# Power_Outlet-RevB.net
KiCad netlist of a schematic drawn in EAGLE
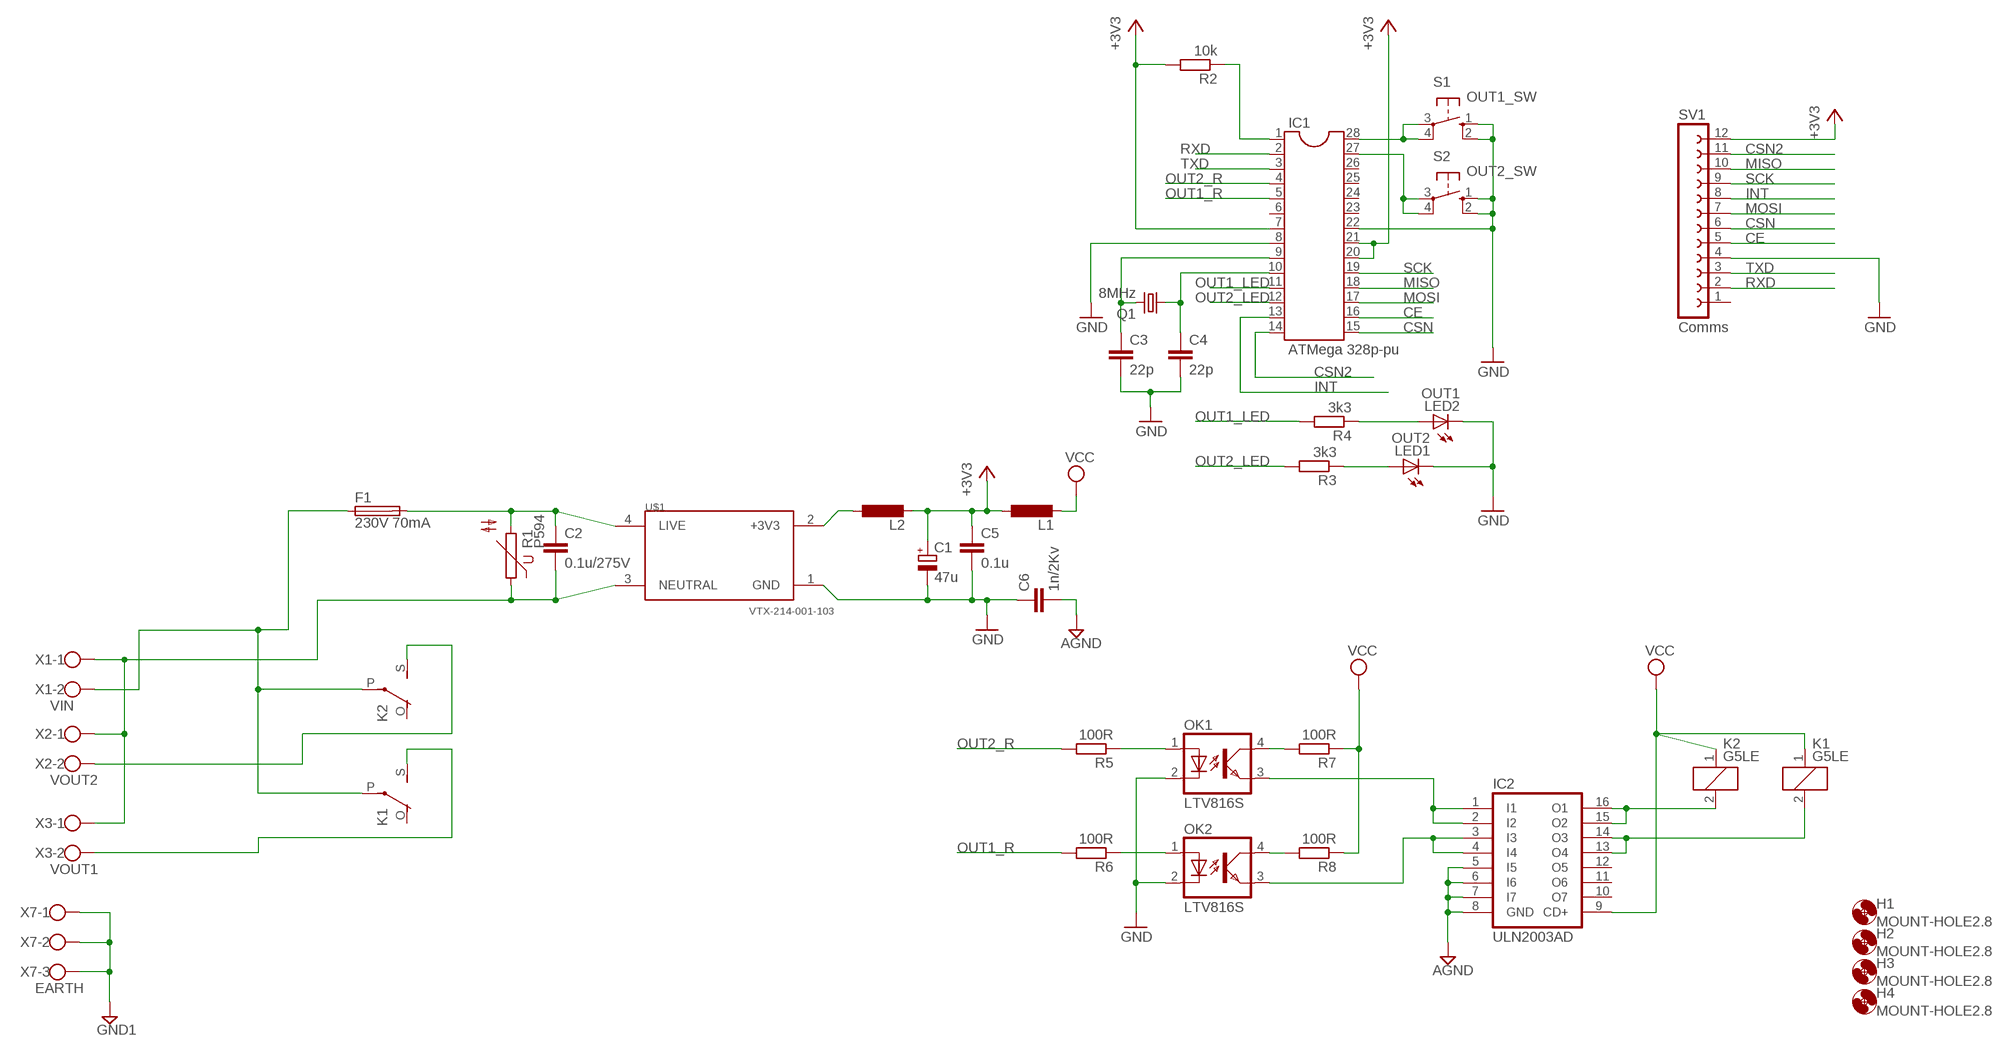
[diagram p0: schematic, sheet 1]

(export (version "E")
  (design (tool "Eeschema 10.0.6"))
  (components
    (comp (ref "C1")
      (value "47u")
      (footprint "eagle-import:E2,5-6E")
      (libsource (lib "eagle-import") (part "CPOL-EUE2,5-6E"))
    )
    (comp (ref "C2")
      (value "0.1u/275V")
      (footprint "eagle-import:C050-030X075")
      (libsource (lib "eagle-import") (part "C-EU050-030X075"))
    )
    (comp (ref "C3")
      (value "22p")
      (footprint "eagle-import:C1206K")
      (libsource (lib "eagle-import") (part "C-EUC1206K"))
    )
    (comp (ref "C4")
      (value "22p")
      (footprint "eagle-import:C1206K")
      (libsource (lib "eagle-import") (part "C-EUC1206K"))
    )
    (comp (ref "C5")
      (value "0.1u")
      (footprint "eagle-import:C1206K")
      (libsource (lib "eagle-import") (part "C-EUC1206K"))
    )
    (comp (ref "C6")
      (value "1n/2Kv")
      (footprint "eagle-import:C1206K")
      (libsource (lib "eagle-import") (part "C-EUC1206K"))
    )
    (comp (ref "F1")
      (value "230V 70mA")
      (footprint "eagle-import:SH22,5A")
      (libsource (lib "eagle-import") (part "FUSESH22,5A"))
    )
    (comp (ref "H1")
      (value "MOUNT-HOLE2.8")
      (footprint "eagle-import:2,8")
      (libsource (lib "eagle-import") (part "MOUNT-HOLE2.8"))
    )
    (comp (ref "H2")
      (value "MOUNT-HOLE2.8")
      (footprint "eagle-import:2,8")
      (libsource (lib "eagle-import") (part "MOUNT-HOLE2.8"))
    )
    (comp (ref "H3")
      (value "MOUNT-HOLE2.8")
      (footprint "eagle-import:2,8")
      (libsource (lib "eagle-import") (part "MOUNT-HOLE2.8"))
    )
    (comp (ref "H4")
      (value "MOUNT-HOLE2.8")
      (footprint "eagle-import:2,8")
      (libsource (lib "eagle-import") (part "MOUNT-HOLE2.8"))
    )
    (comp (ref "IC1")
      (value "ATMega 328p-pu")
      (footprint "eagle-import:DIL28-3")
      (libsource (lib "eagle-import") (part "DIL28-3"))
    )
    (comp (ref "IC2")
      (value "ULN2003AD")
      (footprint "eagle-import:SO16")
      (libsource (lib "eagle-import") (part "ULN2003AD"))
    )
    (comp (ref "K1")
      (value "G5LE")
      (footprint "eagle-import:G5LE")
      (libsource (lib "eagle-import") (part "G5LE"))
    )
    (comp (ref "K2")
      (value "G5LE")
      (footprint "eagle-import:G5LE")
      (libsource (lib "eagle-import") (part "G5LE"))
    )
    (comp (ref "L1")
      (value "L-EUL3225P")
      (footprint "eagle-import:L3225P")
      (libsource (lib "eagle-import") (part "L-EUL3225P"))
    )
    (comp (ref "L2")
      (value "L-EUL3225P")
      (footprint "eagle-import:L3225P")
      (libsource (lib "eagle-import") (part "L-EUL3225P"))
    )
    (comp (ref "LED1")
      (value "OUT2")
      (footprint "eagle-import:LED5MM")
      (libsource (lib "eagle-import") (part "LED5MM"))
    )
    (comp (ref "LED2")
      (value "OUT1")
      (footprint "eagle-import:LED5MM")
      (libsource (lib "eagle-import") (part "LED5MM"))
    )
    (comp (ref "OK1")
      (value "LTV816S")
      (footprint "eagle-import:SMD4")
      (libsource (lib "eagle-import") (part "LTV816S"))
    )
    (comp (ref "OK2")
      (value "LTV816S")
      (footprint "eagle-import:SMD4")
      (libsource (lib "eagle-import") (part "LTV816S"))
    )
    (comp (ref "Q1")
      (value "8MHz")
      (footprint "eagle-import:HC49_S")
      (libsource (lib "eagle-import") (part "CRYSTALHC49S"))
    )
    (comp (ref "R1")
      (value "P594")
      (footprint "eagle-import:P594")
      (libsource (lib "eagle-import") (part "P594"))
    )
    (comp (ref "R2")
      (value "10k")
      (footprint "eagle-import:R1206W")
      (libsource (lib "eagle-import") (part "R-EU_R1206W"))
    )
    (comp (ref "R3")
      (value "3k3")
      (footprint "eagle-import:R1206W")
      (libsource (lib "eagle-import") (part "R-EU_R1206W"))
    )
    (comp (ref "R4")
      (value "3k3")
      (footprint "eagle-import:R1206W")
      (libsource (lib "eagle-import") (part "R-EU_R1206W"))
    )
    (comp (ref "R5")
      (value "100R")
      (footprint "eagle-import:R1206W")
      (libsource (lib "eagle-import") (part "R-EU_R1206W"))
    )
    (comp (ref "R6")
      (value "100R")
      (footprint "eagle-import:R1206W")
      (libsource (lib "eagle-import") (part "R-EU_R1206W"))
    )
    (comp (ref "R7")
      (value "100R")
      (footprint "eagle-import:R1206W")
      (libsource (lib "eagle-import") (part "R-EU_R1206W"))
    )
    (comp (ref "R8")
      (value "100R")
      (footprint "eagle-import:R1206W")
      (libsource (lib "eagle-import") (part "R-EU_R1206W"))
    )
    (comp (ref "S1")
      (value "OUT1_SW")
      (footprint "eagle-import:B3F-40XX")
      (fields (field (name "MF") "OMRON COMPONENTS USA") (field (name "MPN") "B3F-4000"))
      (libsource (lib "eagle-import") (part "40-XX"))
    )
    (comp (ref "S2")
      (value "OUT2_SW")
      (footprint "eagle-import:B3F-40XX")
      (fields (field (name "MF") "OMRON COMPONENTS USA") (field (name "MPN") "B3F-4000"))
      (libsource (lib "eagle-import") (part "40-XX"))
    )
    (comp (ref "SV1")
      (value "Comms")
      (footprint "eagle-import:FE12W")
      (libsource (lib "eagle-import") (part "FE12W"))
    )
    (comp (ref "U$1")
      (value "VTX-214-001-103")
      (footprint "eagle-import:VTX214001103")
      (libsource (lib "eagle-import") (part "VTX-214-001-103"))
    )
    (comp (ref "X1")
      (value "VIN")
      (footprint "eagle-import:W237-102")
      (fields (field (name "MPN") "237-102"))
      (libsource (lib "eagle-import") (part "W237-102"))
    )
    (comp (ref "X2")
      (value "VOUT2")
      (footprint "eagle-import:W237-102")
      (fields (field (name "MPN") "237-102"))
      (libsource (lib "eagle-import") (part "W237-102"))
    )
    (comp (ref "X3")
      (value "VOUT1")
      (footprint "eagle-import:W237-102")
      (fields (field (name "MPN") "237-102"))
      (libsource (lib "eagle-import") (part "W237-102"))
    )
    (comp (ref "X7")
      (value "EARTH")
      (footprint "eagle-import:W237-103")
      (fields (field (name "MPN") "237-103"))
      (libsource (lib "eagle-import") (part "W237-103"))
    )
  )
  (nets
    (net (code "1") (name "+3V3") (class "Default")
      (node (ref "C1") (pin "+") (pinfunction "+_+") (pintype "passive"))
      (node (ref "C5") (pin "1") (pinfunction "1_1") (pintype "passive"))
      (node (ref "IC1") (pin "20") (pinfunction "20_20") (pintype "passive"))
      (node (ref "IC1") (pin "21") (pinfunction "21_21") (pintype "passive"))
      (node (ref "IC1") (pin "7") (pinfunction "7_7") (pintype "passive"))
      (node (ref "L1") (pin "1") (pinfunction "1_1") (pintype "passive"))
      (node (ref "L2") (pin "1") (pinfunction "1_1") (pintype "passive"))
      (node (ref "L2") (pin "2") (pinfunction "2_2") (pintype "passive"))
      (node (ref "R2") (pin "2") (pinfunction "2_2") (pintype "passive"))
      (node (ref "SV1") (pin "12") (pinfunction "12_12") (pintype "passive"))
      (node (ref "U$1") (pin "2") (pinfunction "+3V3_2") (pintype "power_in"))
    )
    (net (code "2") (name "/CE") (class "Default")
      (node (ref "IC1") (pin "16") (pinfunction "16_16") (pintype "passive"))
      (node (ref "SV1") (pin "5") (pinfunction "5_5") (pintype "passive"))
    )
    (net (code "3") (name "/CSN") (class "Default")
      (node (ref "IC1") (pin "15") (pinfunction "15_15") (pintype "passive"))
      (node (ref "SV1") (pin "6") (pinfunction "6_6") (pintype "passive"))
    )
    (net (code "4") (name "/CSN2") (class "Default")
      (node (ref "IC1") (pin "14") (pinfunction "14_14") (pintype "passive"))
      (node (ref "SV1") (pin "11") (pinfunction "11_11") (pintype "passive"))
    )
    (net (code "5") (name "/INT") (class "Default")
      (node (ref "IC1") (pin "13") (pinfunction "13_13") (pintype "passive"))
      (node (ref "SV1") (pin "8") (pinfunction "8_8") (pintype "passive"))
    )
    (net (code "6") (name "/MISO") (class "Default")
      (node (ref "IC1") (pin "18") (pinfunction "18_18") (pintype "passive"))
      (node (ref "SV1") (pin "10") (pinfunction "10_10") (pintype "passive"))
    )
    (net (code "7") (name "/MOSI") (class "Default")
      (node (ref "IC1") (pin "17") (pinfunction "17_17") (pintype "passive"))
      (node (ref "SV1") (pin "7") (pinfunction "7_7") (pintype "passive"))
    )
    (net (code "8") (name "/OUT1_LED") (class "Default")
      (node (ref "IC1") (pin "11") (pinfunction "11_11") (pintype "passive"))
      (node (ref "R4") (pin "2") (pinfunction "2_2") (pintype "passive"))
    )
    (net (code "9") (name "/OUT1_R") (class "Default")
      (node (ref "IC1") (pin "5") (pinfunction "5_5") (pintype "passive"))
      (node (ref "R6") (pin "2") (pinfunction "2_2") (pintype "passive"))
    )
    (net (code "10") (name "/OUT2_LED") (class "Default")
      (node (ref "IC1") (pin "12") (pinfunction "12_12") (pintype "passive"))
      (node (ref "R3") (pin "2") (pinfunction "2_2") (pintype "passive"))
    )
    (net (code "11") (name "/OUT2_R") (class "Default")
      (node (ref "IC1") (pin "4") (pinfunction "4_4") (pintype "passive"))
      (node (ref "R5") (pin "2") (pinfunction "2_2") (pintype "passive"))
    )
    (net (code "12") (name "/RXD") (class "Default")
      (node (ref "IC1") (pin "2") (pinfunction "2_2") (pintype "passive"))
      (node (ref "SV1") (pin "2") (pinfunction "2_2") (pintype "passive"))
    )
    (net (code "13") (name "/SCK") (class "Default")
      (node (ref "IC1") (pin "19") (pinfunction "19_19") (pintype "passive"))
      (node (ref "SV1") (pin "9") (pinfunction "9_9") (pintype "passive"))
    )
    (net (code "14") (name "/TXD") (class "Default")
      (node (ref "IC1") (pin "3") (pinfunction "3_3") (pintype "passive"))
      (node (ref "SV1") (pin "3") (pinfunction "3_3") (pintype "passive"))
    )
    (net (code "15") (name "AGND") (class "Default")
      (node (ref "C6") (pin "2") (pinfunction "2_2") (pintype "passive"))
      (node (ref "IC2") (pin "5") (pinfunction "I5_5") (pintype "input"))
      (node (ref "IC2") (pin "6") (pinfunction "I6_6") (pintype "input"))
      (node (ref "IC2") (pin "7") (pinfunction "I7_7") (pintype "input"))
      (node (ref "IC2") (pin "8") (pinfunction "GND_8") (pintype "power_in"))
    )
    (net (code "16") (name "GND") (class "Default")
      (node (ref "C1") (pin "-") (pinfunction "-_-") (pintype "passive"))
      (node (ref "C3") (pin "2") (pinfunction "2_2") (pintype "passive"))
      (node (ref "C4") (pin "2") (pinfunction "2_2") (pintype "passive"))
      (node (ref "C5") (pin "2") (pinfunction "2_2") (pintype "passive"))
      (node (ref "C6") (pin "1") (pinfunction "1_1") (pintype "passive"))
      (node (ref "IC1") (pin "22") (pinfunction "22_22") (pintype "passive"))
      (node (ref "IC1") (pin "8") (pinfunction "8_8") (pintype "passive"))
      (node (ref "LED1") (pin "K") (pinfunction "C_K") (pintype "passive"))
      (node (ref "LED2") (pin "K") (pinfunction "C_K") (pintype "passive"))
      (node (ref "OK1") (pin "2") (pinfunction "C_2") (pintype "passive"))
      (node (ref "OK2") (pin "2") (pinfunction "C_2") (pintype "passive"))
      (node (ref "S1") (pin "1") (pinfunction "S_1") (pintype "passive"))
      (node (ref "S1") (pin "2") (pinfunction "S1_2") (pintype "passive"))
      (node (ref "S2") (pin "1") (pinfunction "S_1") (pintype "passive"))
      (node (ref "S2") (pin "2") (pinfunction "S1_2") (pintype "passive"))
      (node (ref "SV1") (pin "4") (pinfunction "4_4") (pintype "passive"))
      (node (ref "U$1") (pin "1") (pinfunction "GND_1") (pintype "power_in"))
    )
    (net (code "17") (name "GND1") (class "Default")
      (node (ref "X7") (pin "1") (pinfunction "KL_1") (pintype "passive"))
      (node (ref "X7") (pin "2") (pinfunction "KL_2") (pintype "passive"))
      (node (ref "X7") (pin "3") (pinfunction "KL_3") (pintype "passive"))
    )
    (net (code "18") (name "Net-(C3-Pad1)") (class "Default")
      (node (ref "C3") (pin "1") (pinfunction "1_1") (pintype "passive"))
      (node (ref "IC1") (pin "9") (pinfunction "9_9") (pintype "passive"))
      (node (ref "Q1") (pin "2") (pinfunction "2_2") (pintype "passive"))
    )
    (net (code "19") (name "Net-(C4-Pad1)") (class "Default")
      (node (ref "C4") (pin "1") (pinfunction "1_1") (pintype "passive"))
      (node (ref "IC1") (pin "10") (pinfunction "10_10") (pintype "passive"))
      (node (ref "Q1") (pin "1") (pinfunction "1_1") (pintype "passive"))
    )
    (net (code "20") (name "Net-(IC1-Pad1)") (class "Default")
      (node (ref "IC1") (pin "1") (pinfunction "1_1") (pintype "passive"))
      (node (ref "R2") (pin "1") (pinfunction "1_1") (pintype "passive"))
    )
    (net (code "21") (name "Net-(IC2-I1)") (class "Default")
      (node (ref "IC2") (pin "1") (pinfunction "I1_1") (pintype "input"))
      (node (ref "IC2") (pin "2") (pinfunction "I2_2") (pintype "input"))
      (node (ref "OK1") (pin "3") (pinfunction "EMIT_3") (pintype "passive"))
    )
    (net (code "22") (name "Net-(IC2-I3)") (class "Default")
      (node (ref "IC2") (pin "3") (pinfunction "I3_3") (pintype "input"))
      (node (ref "IC2") (pin "4") (pinfunction "I4_4") (pintype "input"))
      (node (ref "OK2") (pin "3") (pinfunction "EMIT_3") (pintype "passive"))
    )
    (net (code "23") (name "Net-(IC2-O1)") (class "Default")
      (node (ref "IC2") (pin "15") (pinfunction "O2_15") (pintype "open_collector"))
      (node (ref "IC2") (pin "16") (pinfunction "O1_16") (pintype "open_collector"))
      (node (ref "K2") (pin "2") (pinfunction "2_2") (pintype "passive"))
    )
    (net (code "24") (name "Net-(IC2-O3)") (class "Default")
      (node (ref "IC2") (pin "13") (pinfunction "O4_13") (pintype "open_collector"))
      (node (ref "IC2") (pin "14") (pinfunction "O3_14") (pintype "open_collector"))
      (node (ref "K1") (pin "2") (pinfunction "2_2") (pintype "passive"))
    )
    (net (code "25") (name "Net-(LED1-PadA)") (class "Default")
      (node (ref "LED1") (pin "A") (pinfunction "A_A") (pintype "passive"))
      (node (ref "R3") (pin "1") (pinfunction "1_1") (pintype "passive"))
    )
    (net (code "26") (name "Net-(LED2-PadA)") (class "Default")
      (node (ref "LED2") (pin "A") (pinfunction "A_A") (pintype "passive"))
      (node (ref "R4") (pin "1") (pinfunction "1_1") (pintype "passive"))
    )
    (net (code "27") (name "Net-(OK1-A)") (class "Default")
      (node (ref "OK1") (pin "1") (pinfunction "A_1") (pintype "passive"))
      (node (ref "R5") (pin "1") (pinfunction "1_1") (pintype "passive"))
    )
    (net (code "28") (name "Net-(OK1-COL)") (class "Default")
      (node (ref "OK1") (pin "4") (pinfunction "COL_4") (pintype "passive"))
      (node (ref "R7") (pin "2") (pinfunction "2_2") (pintype "passive"))
    )
    (net (code "29") (name "Net-(OK2-A)") (class "Default")
      (node (ref "OK2") (pin "1") (pinfunction "A_1") (pintype "passive"))
      (node (ref "R6") (pin "1") (pinfunction "1_1") (pintype "passive"))
    )
    (net (code "30") (name "Net-(OK2-COL)") (class "Default")
      (node (ref "OK2") (pin "4") (pinfunction "COL_4") (pintype "passive"))
      (node (ref "R8") (pin "2") (pinfunction "2_2") (pintype "passive"))
    )
    (net (code "31") (name "Net-(S1-P)") (class "Default")
      (node (ref "IC1") (pin "28") (pinfunction "28_28") (pintype "passive"))
      (node (ref "S1") (pin "3") (pinfunction "P_3") (pintype "passive"))
      (node (ref "S1") (pin "4") (pinfunction "P1_4") (pintype "passive"))
    )
    (net (code "32") (name "Net-(S2-P)") (class "Default")
      (node (ref "IC1") (pin "27") (pinfunction "27_27") (pintype "passive"))
      (node (ref "S2") (pin "3") (pinfunction "P_3") (pintype "passive"))
      (node (ref "S2") (pin "4") (pinfunction "P1_4") (pintype "passive"))
    )
    (net (code "33") (name "Net-(U$1-LIVE)") (class "Default")
      (node (ref "C2") (pin "1") (pinfunction "1_1") (pintype "passive"))
      (node (ref "F1") (pin "2") (pinfunction "2_2") (pintype "passive"))
      (node (ref "R1") (pin "2") (pinfunction "2_2") (pintype "passive"))
      (node (ref "U$1") (pin "4") (pinfunction "LIVE_4") (pintype "input"))
    )
    (net (code "34") (name "Net-(U$1-NEUTRAL)") (class "Default")
      (node (ref "C2") (pin "2") (pinfunction "2_2") (pintype "passive"))
      (node (ref "R1") (pin "1") (pinfunction "1_1") (pintype "passive"))
      (node (ref "U$1") (pin "3") (pinfunction "NEUTRAL_3") (pintype "input"))
      (node (ref "X1") (pin "1") (pinfunction "KL_1") (pintype "passive"))
      (node (ref "X2") (pin "1") (pinfunction "KL_1") (pintype "passive"))
      (node (ref "X3") (pin "1") (pinfunction "KL_1") (pintype "passive"))
    )
    (net (code "35") (name "Net-(X1B-KL)") (class "Default")
      (node (ref "F1") (pin "1") (pinfunction "1_1") (pintype "passive"))
      (node (ref "K1") (pin "P") (pinfunction "P_P") (pintype "passive"))
      (node (ref "K2") (pin "P") (pinfunction "P_P") (pintype "passive"))
      (node (ref "X1") (pin "2") (pinfunction "KL_2") (pintype "passive"))
    )
    (net (code "36") (name "Net-(X2B-KL)") (class "Default")
      (node (ref "K2") (pin "S") (pinfunction "S_S") (pintype "passive"))
      (node (ref "X2") (pin "2") (pinfunction "KL_2") (pintype "passive"))
    )
    (net (code "37") (name "Net-(X3B-KL)") (class "Default")
      (node (ref "K1") (pin "S") (pinfunction "S_S") (pintype "passive"))
      (node (ref "X3") (pin "2") (pinfunction "KL_2") (pintype "passive"))
    )
    (net (code "38") (name "VCC") (class "Default")
      (node (ref "IC2") (pin "9") (pinfunction "CD+_9") (pintype "passive"))
      (node (ref "K1") (pin "1") (pinfunction "1_1") (pintype "passive"))
      (node (ref "K2") (pin "1") (pinfunction "1_1") (pintype "passive"))
      (node (ref "L1") (pin "2") (pinfunction "2_2") (pintype "passive"))
      (node (ref "R7") (pin "1") (pinfunction "1_1") (pintype "passive"))
      (node (ref "R8") (pin "1") (pinfunction "1_1") (pintype "passive"))
    )
    (net (code "39") (name "unconnected-(IC1-Pad6)") (class "Default")
      (node (ref "IC1") (pin "6") (pinfunction "6_6") (pintype "passive"))
    )
    (net (code "40") (name "unconnected-(IC1-Pad23)") (class "Default")
      (node (ref "IC1") (pin "23") (pinfunction "23_23") (pintype "passive"))
    )
    (net (code "41") (name "unconnected-(IC1-Pad24)") (class "Default")
      (node (ref "IC1") (pin "24") (pinfunction "24_24") (pintype "passive"))
    )
    (net (code "42") (name "unconnected-(IC1-Pad25)") (class "Default")
      (node (ref "IC1") (pin "25") (pinfunction "25_25") (pintype "passive"))
    )
    (net (code "43") (name "unconnected-(IC1-Pad26)") (class "Default")
      (node (ref "IC1") (pin "26") (pinfunction "26_26") (pintype "passive"))
    )
    (net (code "44") (name "unconnected-(IC2-O5-Pad12)") (class "Default")
      (node (ref "IC2") (pin "12") (pinfunction "O5_12") (pintype "open_collector"))
    )
    (net (code "45") (name "unconnected-(IC2-O6-Pad11)") (class "Default")
      (node (ref "IC2") (pin "11") (pinfunction "O6_11") (pintype "open_collector"))
    )
    (net (code "46") (name "unconnected-(IC2-O7-Pad10)") (class "Default")
      (node (ref "IC2") (pin "10") (pinfunction "O7_10") (pintype "open_collector"))
    )
    (net (code "47") (name "unconnected-(K1-PadO)") (class "Default")
      (node (ref "K1") (pin "O") (pinfunction "O_O") (pintype "passive"))
    )
    (net (code "48") (name "unconnected-(K2-PadO)") (class "Default")
      (node (ref "K2") (pin "O") (pinfunction "O_O") (pintype "passive"))
    )
    (net (code "49") (name "unconnected-(SV1-Pad1)") (class "Default")
      (node (ref "SV1") (pin "1") (pinfunction "1_1") (pintype "passive"))
    )
  )
)
